# Breadboard_Nano_v3.net
KiCad netlist of a schematic drawn in EAGLE
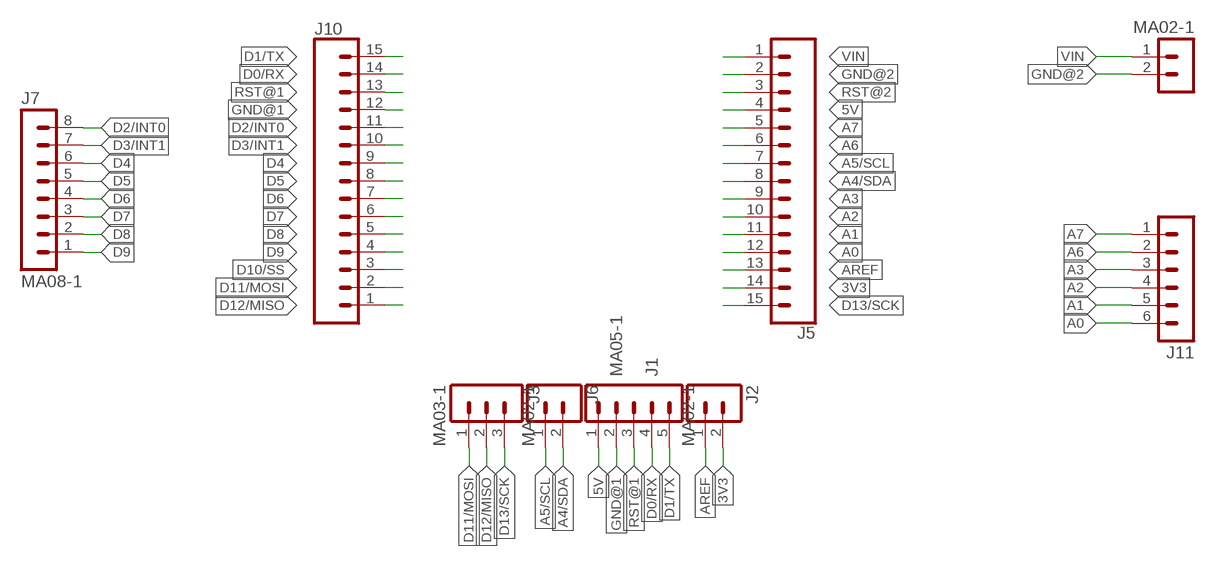
[diagram p0: schematic, sheet 1]

(export (version "E")
  (design (tool "Eeschema 10.0.6"))
  (components
    (comp (ref "J1")
      (value "MA05-1")
      (footprint "eagle-import:MA05-1")
      (libsource (lib "eagle-import") (part "MA05-1"))
    )
    (comp (ref "J2")
      (value "MA02-1")
      (footprint "eagle-import:MA02-1")
      (libsource (lib "eagle-import") (part "MA02-1"))
    )
    (comp (ref "J3")
      (value "MA03-1")
      (footprint "eagle-import:MA03-1")
      (libsource (lib "eagle-import") (part "MA03-1"))
    )
    (comp (ref "J5")
      (value "CONN_15")
      (footprint "eagle-import:1X15")
      (libsource (lib "eagle-import") (part "CONN_15"))
    )
    (comp (ref "J6")
      (value "MA02-1")
      (footprint "eagle-import:MA02-1")
      (libsource (lib "eagle-import") (part "MA02-1"))
    )
    (comp (ref "J7")
      (value "MA08-1")
      (footprint "eagle-import:MA08-1")
      (libsource (lib "eagle-import") (part "MA08-1"))
    )
    (comp (ref "J9")
      (value "MA02-1")
      (footprint "eagle-import:MA02-1")
      (libsource (lib "eagle-import") (part "MA02-1"))
    )
    (comp (ref "J10")
      (value "CONN_15")
      (footprint "eagle-import:1X15")
      (libsource (lib "eagle-import") (part "CONN_15"))
    )
    (comp (ref "J11")
      (value "MA06-1")
      (footprint "eagle-import:MA06-1")
      (libsource (lib "eagle-import") (part "MA06-1"))
    )
  )
  (nets
    (net (code "1") (name "3V3") (class "Default")
      (node (ref "J2") (pin "2") (pinfunction "2_2") (pintype "passive"))
      (node (ref "J5") (pin "14") (pinfunction "14_14") (pintype "passive"))
    )
    (net (code "2") (name "5V") (class "Default")
      (node (ref "J1") (pin "1") (pinfunction "1_1") (pintype "passive"))
      (node (ref "J5") (pin "4") (pinfunction "4_4") (pintype "passive"))
    )
    (net (code "3") (name "A0") (class "Default")
      (node (ref "J11") (pin "6") (pinfunction "6_6") (pintype "passive"))
      (node (ref "J5") (pin "12") (pinfunction "12_12") (pintype "passive"))
    )
    (net (code "4") (name "A1") (class "Default")
      (node (ref "J11") (pin "5") (pinfunction "5_5") (pintype "passive"))
      (node (ref "J5") (pin "11") (pinfunction "11_11") (pintype "passive"))
    )
    (net (code "5") (name "A2") (class "Default")
      (node (ref "J11") (pin "4") (pinfunction "4_4") (pintype "passive"))
      (node (ref "J5") (pin "10") (pinfunction "10_10") (pintype "passive"))
    )
    (net (code "6") (name "A3") (class "Default")
      (node (ref "J11") (pin "3") (pinfunction "3_3") (pintype "passive"))
      (node (ref "J5") (pin "9") (pinfunction "9_9") (pintype "passive"))
    )
    (net (code "7") (name "A4{slash}SDA") (class "Default")
      (node (ref "J5") (pin "8") (pinfunction "8_8") (pintype "passive"))
      (node (ref "J6") (pin "2") (pinfunction "2_2") (pintype "passive"))
    )
    (net (code "8") (name "A5{slash}SCL") (class "Default")
      (node (ref "J5") (pin "7") (pinfunction "7_7") (pintype "passive"))
      (node (ref "J6") (pin "1") (pinfunction "1_1") (pintype "passive"))
    )
    (net (code "9") (name "A6") (class "Default")
      (node (ref "J11") (pin "2") (pinfunction "2_2") (pintype "passive"))
      (node (ref "J5") (pin "6") (pinfunction "6_6") (pintype "passive"))
    )
    (net (code "10") (name "A7") (class "Default")
      (node (ref "J11") (pin "1") (pinfunction "1_1") (pintype "passive"))
      (node (ref "J5") (pin "5") (pinfunction "5_5") (pintype "passive"))
    )
    (net (code "11") (name "AREF") (class "Default")
      (node (ref "J2") (pin "1") (pinfunction "1_1") (pintype "passive"))
      (node (ref "J5") (pin "13") (pinfunction "13_13") (pintype "passive"))
    )
    (net (code "12") (name "D0{slash}RX") (class "Default")
      (node (ref "J1") (pin "4") (pinfunction "4_4") (pintype "passive"))
      (node (ref "J10") (pin "14") (pinfunction "14_14") (pintype "passive"))
    )
    (net (code "13") (name "D1{slash}TX") (class "Default")
      (node (ref "J1") (pin "5") (pinfunction "5_5") (pintype "passive"))
      (node (ref "J10") (pin "15") (pinfunction "15_15") (pintype "passive"))
    )
    (net (code "14") (name "D2{slash}INT0") (class "Default")
      (node (ref "J10") (pin "11") (pinfunction "11_11") (pintype "passive"))
      (node (ref "J7") (pin "8") (pinfunction "8_8") (pintype "passive"))
    )
    (net (code "15") (name "D3{slash}INT1") (class "Default")
      (node (ref "J10") (pin "10") (pinfunction "10_10") (pintype "passive"))
      (node (ref "J7") (pin "7") (pinfunction "7_7") (pintype "passive"))
    )
    (net (code "16") (name "D4") (class "Default")
      (node (ref "J10") (pin "9") (pinfunction "9_9") (pintype "passive"))
      (node (ref "J7") (pin "6") (pinfunction "6_6") (pintype "passive"))
    )
    (net (code "17") (name "D5") (class "Default")
      (node (ref "J10") (pin "8") (pinfunction "8_8") (pintype "passive"))
      (node (ref "J7") (pin "5") (pinfunction "5_5") (pintype "passive"))
    )
    (net (code "18") (name "D6") (class "Default")
      (node (ref "J10") (pin "7") (pinfunction "7_7") (pintype "passive"))
      (node (ref "J7") (pin "4") (pinfunction "4_4") (pintype "passive"))
    )
    (net (code "19") (name "D7") (class "Default")
      (node (ref "J10") (pin "6") (pinfunction "6_6") (pintype "passive"))
      (node (ref "J7") (pin "3") (pinfunction "3_3") (pintype "passive"))
    )
    (net (code "20") (name "D8") (class "Default")
      (node (ref "J10") (pin "5") (pinfunction "5_5") (pintype "passive"))
      (node (ref "J7") (pin "2") (pinfunction "2_2") (pintype "passive"))
    )
    (net (code "21") (name "D9") (class "Default")
      (node (ref "J10") (pin "4") (pinfunction "4_4") (pintype "passive"))
      (node (ref "J7") (pin "1") (pinfunction "1_1") (pintype "passive"))
    )
    (net (code "22") (name "D10{slash}SS") (class "Default")
      (node (ref "J10") (pin "3") (pinfunction "3_3") (pintype "passive"))
    )
    (net (code "23") (name "D11{slash}MOSI") (class "Default")
      (node (ref "J10") (pin "2") (pinfunction "2_2") (pintype "passive"))
      (node (ref "J3") (pin "1") (pinfunction "1_1") (pintype "passive"))
    )
    (net (code "24") (name "D12{slash}MISO") (class "Default")
      (node (ref "J10") (pin "1") (pinfunction "1_1") (pintype "passive"))
      (node (ref "J3") (pin "2") (pinfunction "2_2") (pintype "passive"))
    )
    (net (code "25") (name "D13{slash}SCK") (class "Default")
      (node (ref "J3") (pin "3") (pinfunction "3_3") (pintype "passive"))
      (node (ref "J5") (pin "15") (pinfunction "15_15") (pintype "passive"))
    )
    (net (code "26") (name "GND@1") (class "Default")
      (node (ref "J1") (pin "2") (pinfunction "2_2") (pintype "passive"))
      (node (ref "J10") (pin "12") (pinfunction "12_12") (pintype "passive"))
    )
    (net (code "27") (name "GND@2") (class "Default")
      (node (ref "J5") (pin "2") (pinfunction "2_2") (pintype "passive"))
      (node (ref "J9") (pin "2") (pinfunction "2_2") (pintype "passive"))
    )
    (net (code "28") (name "RST@1") (class "Default")
      (node (ref "J1") (pin "3") (pinfunction "3_3") (pintype "passive"))
      (node (ref "J10") (pin "13") (pinfunction "13_13") (pintype "passive"))
    )
    (net (code "29") (name "RST@2") (class "Default")
      (node (ref "J5") (pin "3") (pinfunction "3_3") (pintype "passive"))
    )
    (net (code "30") (name "VIN") (class "Default")
      (node (ref "J5") (pin "1") (pinfunction "1_1") (pintype "passive"))
      (node (ref "J9") (pin "1") (pinfunction "1_1") (pintype "passive"))
    )
  )
)
